# PCB-IO-PROTECTION-1.net
KiCad netlist of a schematic drawn in Altium Designer
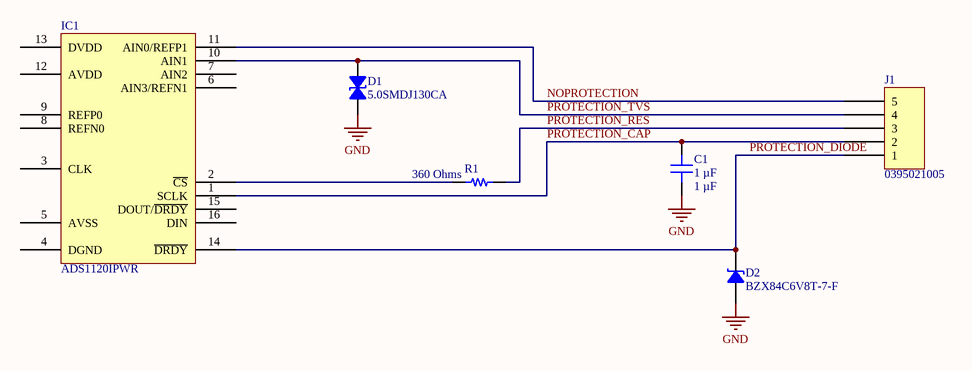
[diagram p0: PCB-IO-PROTECTION-1.SchDoc]

(export (version "E")
  (design (tool "Eeschema 10.0.6"))
  (components
    (comp (ref "C1")
      (value "1 µF")
      (footprint "CAP 0603_1608")
      (description "CAP CER 1UF 16V X7R 0603")
      (fields (field (name "PART NUMBER") "C0603C105K4RACAUTO") (field (name "ALTIUM_VALUE") "1 µF"))
      (libsource (lib "Celestial Altium Library - altium_library") (part "Capacitor"))
    )
    (comp (ref "D1")
      (value "5.0SMDJ130CA")
      (footprint "DO214AB SMC")
      (description "TVS DIODE 130VWM 209VC DO214AB")
      (libsource (lib "Celestial Altium Library - altium_library") (part "Diode TVS"))
    )
    (comp (ref "D2")
      (value "BZX84C6V8T-7-F")
      (footprint "DIODES SOT-523")
      (description "DIODE ZENER 6.8V 150MW SOT523")
      (libsource (lib "Celestial Altium Library - altium_library") (part "Diode Zener"))
    )
    (comp (ref "IC1")
      (value "ADS1120IPWR")
      (footprint "TI TSSOP-16 PW")
      (description "IC ADC 16BIT SIGMA-DELTA 16TSSOP")
      (libsource (lib "Celestial Altium Library - altium_library") (part "TI ADS1120 TSSOP"))
    )
    (comp (ref "J1")
      (value "0395021005")
      (footprint "MOLEX 395021005")
      (description "TERM BLOCK HDR 5POS 90DEG 3.5MM")
      (libsource (lib "Celestial Altium Library - altium_library") (part "5 Pin"))
    )
    (comp (ref "R1")
      (value "360 Ohms")
      (footprint "RES 0603_1608")
      (description "RES SMD 360 OHM 0.1% 1/5W 0603")
      (fields (field (name "PART NUMBER") "ERJ-PB3B3600V"))
      (libsource (lib "Celestial Altium Library - altium_library") (part "Resistor"))
    )
  )
  (nets
    (net (code "1") (name "/NOPROTECTION") (class "Default")
      (node (ref "IC1") (pin "11") (pinfunction "AIN0/REFP1_11") (pintype "passive"))
      (node (ref "J1") (pin "5") (pinfunction "5_5") (pintype "passive"))
    )
    (net (code "2") (name "/PROTECTION_CAP") (class "Default")
      (node (ref "C1") (pin "2") (pinfunction "2_2") (pintype "passive"))
      (node (ref "IC1") (pin "1") (pinfunction "SCLK_1") (pintype "passive"))
      (node (ref "J1") (pin "2") (pinfunction "2_2") (pintype "passive"))
    )
    (net (code "3") (name "/PROTECTION_DIODE") (class "Default")
      (node (ref "D2") (pin "2") (pinfunction "2_2") (pintype "passive"))
      (node (ref "IC1") (pin "14") (pinfunction "~{DRDY}_14") (pintype "passive"))
      (node (ref "J1") (pin "1") (pinfunction "1_1") (pintype "passive"))
    )
    (net (code "4") (name "/PROTECTION_RES") (class "Default")
      (node (ref "J1") (pin "3") (pinfunction "3_3") (pintype "passive"))
      (node (ref "R1") (pin "2") (pinfunction "2_2") (pintype "passive"))
    )
    (net (code "5") (name "/PROTECTION_TVS") (class "Default")
      (node (ref "D1") (pin "2") (pinfunction "2_2") (pintype "passive"))
      (node (ref "IC1") (pin "10") (pinfunction "AIN1_10") (pintype "passive"))
      (node (ref "J1") (pin "4") (pinfunction "4_4") (pintype "passive"))
    )
    (net (code "6") (name "GND") (class "Default")
      (node (ref "C1") (pin "1") (pinfunction "1_1") (pintype "passive"))
      (node (ref "D1") (pin "1") (pinfunction "1_1") (pintype "passive"))
      (node (ref "D2") (pin "1") (pinfunction "1_1") (pintype "passive"))
    )
    (net (code "7") (name "Net-(IC1-~{CS})") (class "Default")
      (node (ref "IC1") (pin "2") (pinfunction "~{CS}_2") (pintype "passive"))
      (node (ref "R1") (pin "1") (pinfunction "1_1") (pintype "passive"))
    )
    (net (code "8") (name "unconnected-(IC1-AIN2-Pad7)") (class "Default")
      (node (ref "IC1") (pin "7") (pinfunction "AIN2_7") (pintype "passive"))
    )
    (net (code "9") (name "unconnected-(IC1-AIN3{slash}REFN1-Pad6)") (class "Default")
      (node (ref "IC1") (pin "6") (pinfunction "AIN3/REFN1_6") (pintype "passive"))
    )
    (net (code "10") (name "unconnected-(IC1-AVDD-Pad12)") (class "Default")
      (node (ref "IC1") (pin "12") (pinfunction "AVDD_12") (pintype "passive"))
    )
    (net (code "11") (name "unconnected-(IC1-AVSS-Pad5)") (class "Default")
      (node (ref "IC1") (pin "5") (pinfunction "AVSS_5") (pintype "passive"))
    )
    (net (code "12") (name "unconnected-(IC1-CLK-Pad3)") (class "Default")
      (node (ref "IC1") (pin "3") (pinfunction "CLK_3") (pintype "passive"))
    )
    (net (code "13") (name "unconnected-(IC1-DGND-Pad4)") (class "Default")
      (node (ref "IC1") (pin "4") (pinfunction "DGND_4") (pintype "passive"))
    )
    (net (code "14") (name "unconnected-(IC1-DIN-Pad16)") (class "Default")
      (node (ref "IC1") (pin "16") (pinfunction "DIN_16") (pintype "passive"))
    )
    (net (code "15") (name "unconnected-(IC1-DOUT{slash}~{DRDY}-Pad15)") (class "Default")
      (node (ref "IC1") (pin "15") (pinfunction "DOUT/~{DRDY}_15") (pintype "passive"))
    )
    (net (code "16") (name "unconnected-(IC1-DVDD-Pad13)") (class "Default")
      (node (ref "IC1") (pin "13") (pinfunction "DVDD_13") (pintype "passive"))
    )
    (net (code "17") (name "unconnected-(IC1-REFN0-Pad8)") (class "Default")
      (node (ref "IC1") (pin "8") (pinfunction "REFN0_8") (pintype "passive"))
    )
    (net (code "18") (name "unconnected-(IC1-REFP0-Pad9)") (class "Default")
      (node (ref "IC1") (pin "9") (pinfunction "REFP0_9") (pintype "passive"))
    )
  )
)
